# SCH_Schema_Sensoren_2022-11-04.net
KiCad netlist of a schematic drawn in EasyEDA
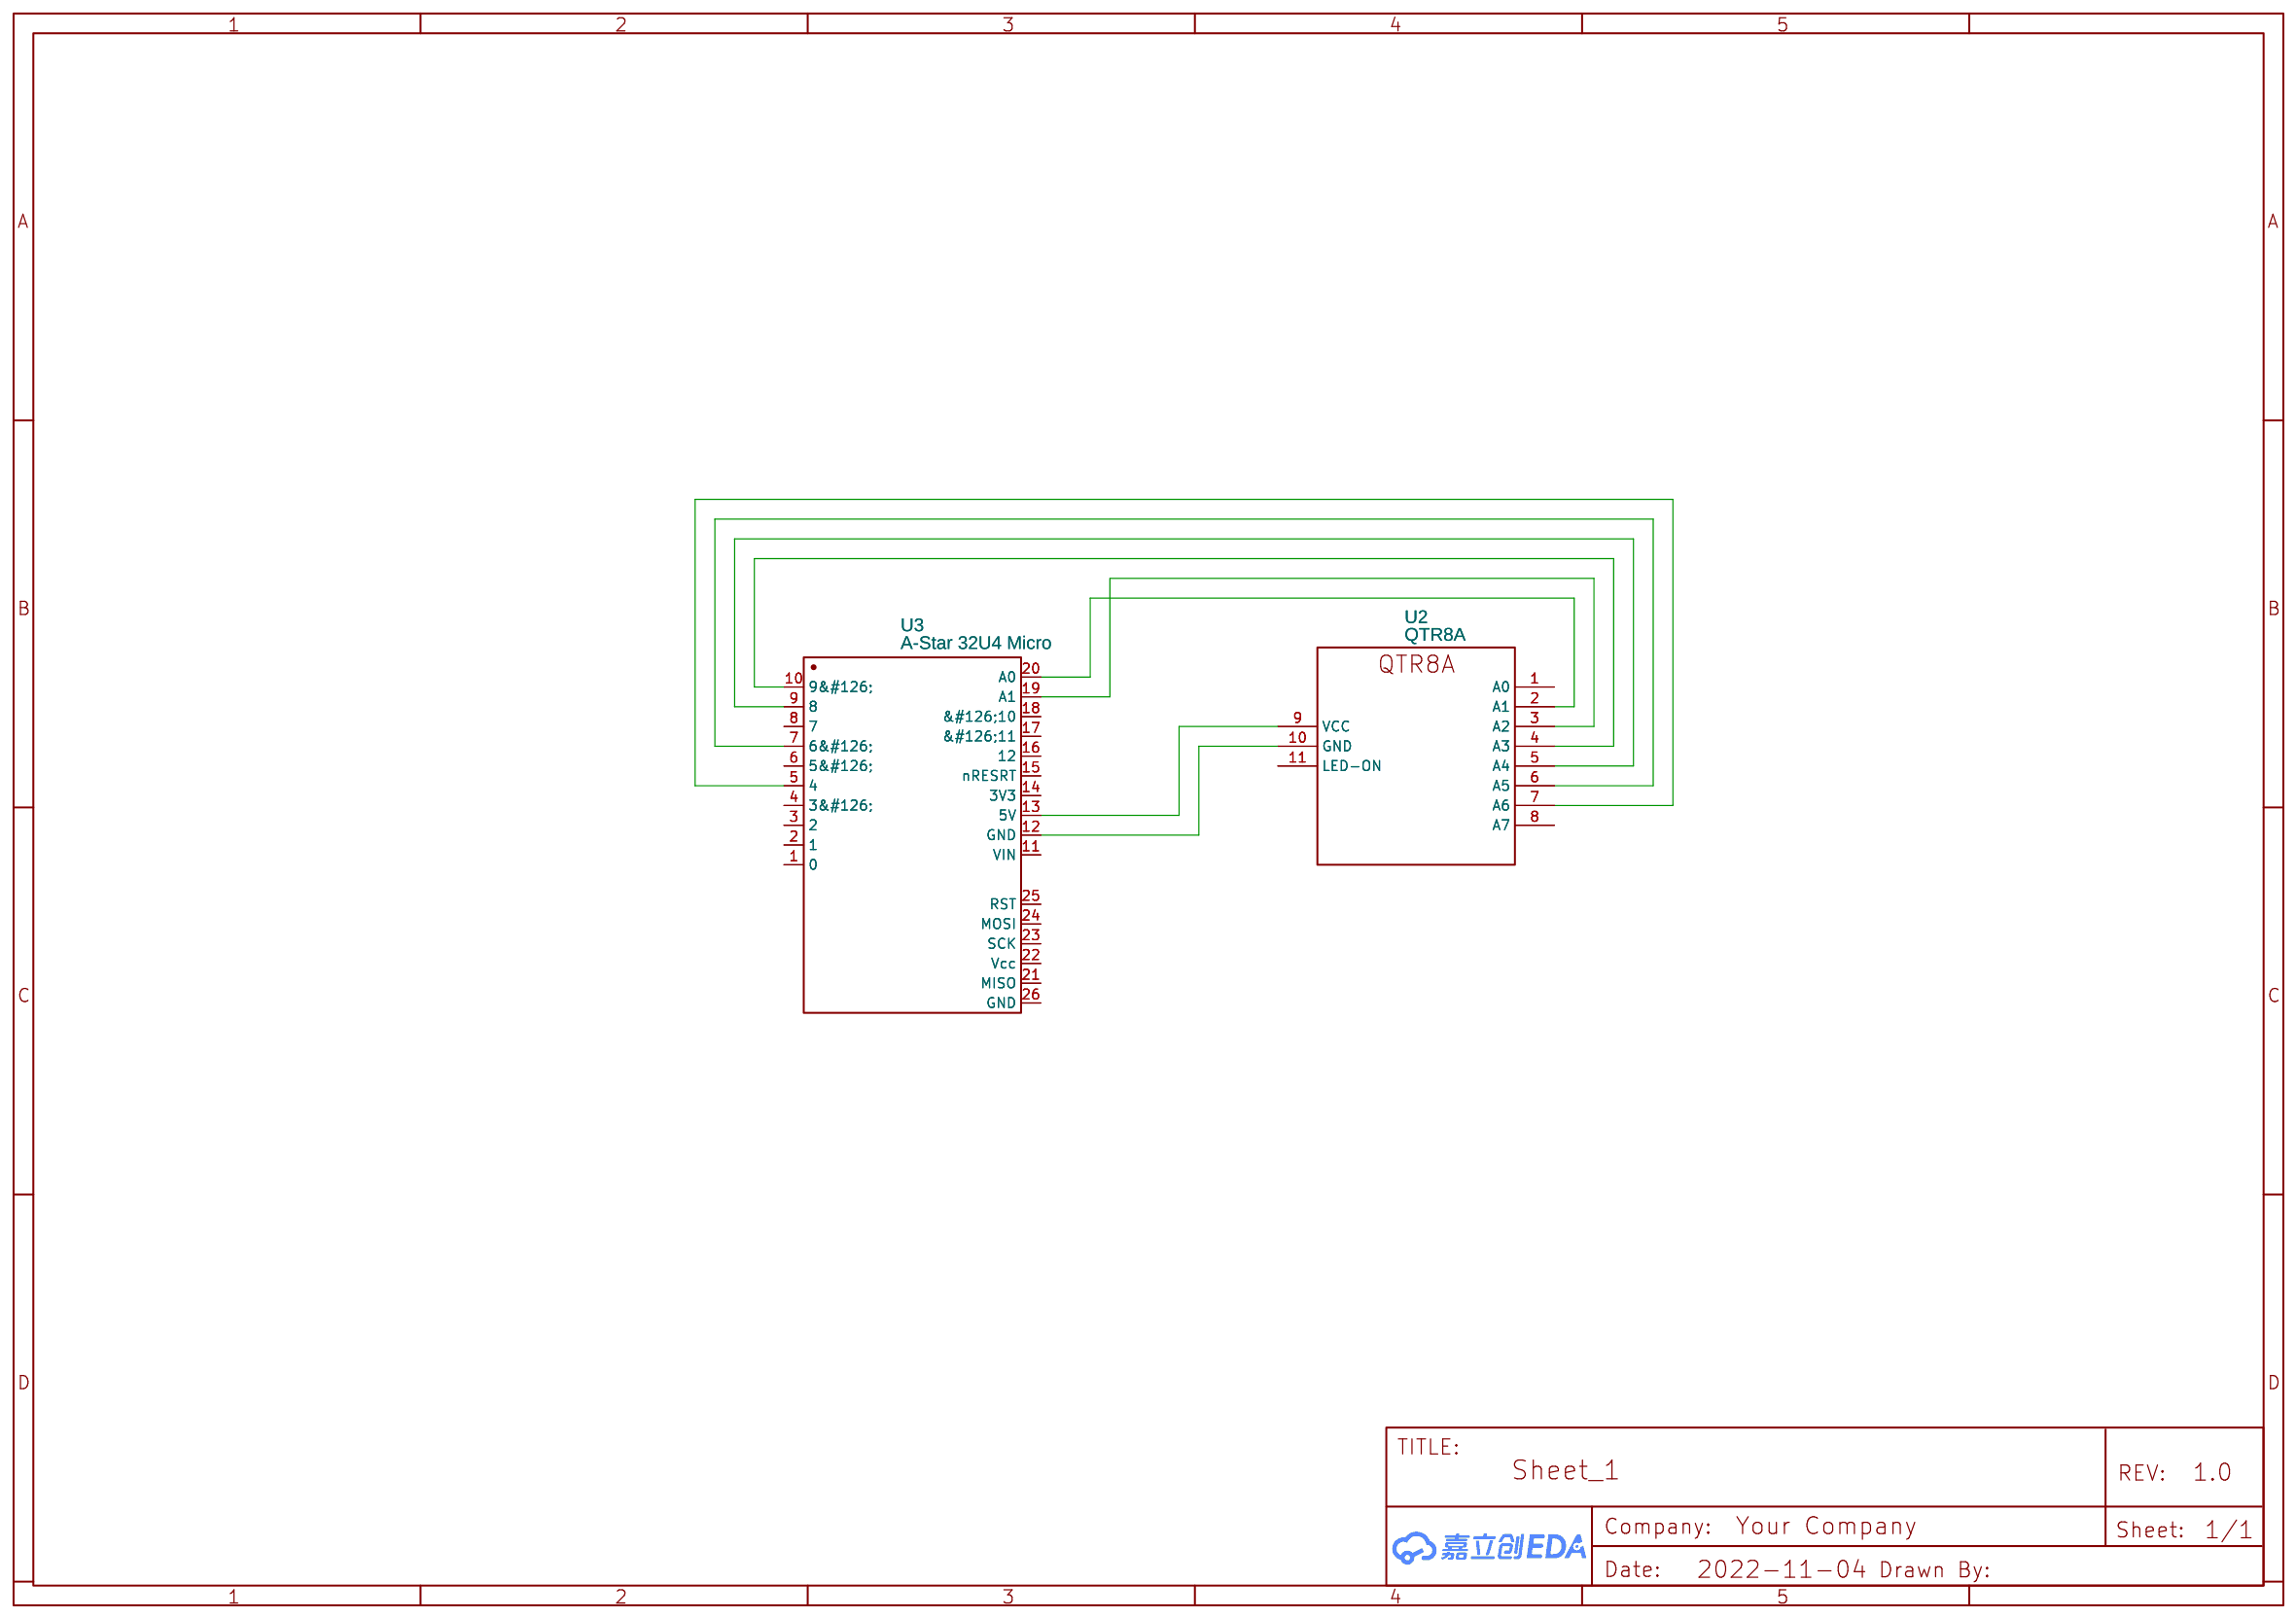
[diagram p0: schematic sheet]

(export (version "E")
  (design (tool "Eeschema 10.0.6"))
  (components
    (comp (ref "U2") (value "QTR8A") (libsource (lib "") (part "QTR8A")))
    (comp (ref "U3")
      (value "A-Star 32U4 Micro")
      (fields (field (name "BOM_Manufacturer Part") "3101"))
      (libsource (lib "") (part "A-Star 32U4 Micro"))
    )
  )
  (nets
    (net (code "1") (name "Net-(U2-A1)") (class "Default")
      (node (ref "U2") (pin "2") (pinfunction "A1_2") (pintype "unspecified"))
      (node (ref "U3") (pin "20") (pinfunction "A0_20") (pintype "unspecified"))
    )
    (net (code "2") (name "Net-(U2-A2)") (class "Default")
      (node (ref "U2") (pin "3") (pinfunction "A2_3") (pintype "unspecified"))
      (node (ref "U3") (pin "19") (pinfunction "A1_19") (pintype "unspecified"))
    )
    (net (code "3") (name "Net-(U2-A3)") (class "Default")
      (node (ref "U2") (pin "4") (pinfunction "A3_4") (pintype "unspecified"))
      (node (ref "U3") (pin "10") (pinfunction "9&#126;_10") (pintype "unspecified"))
    )
    (net (code "4") (name "Net-(U2-A4)") (class "Default")
      (node (ref "U2") (pin "5") (pinfunction "A4_5") (pintype "unspecified"))
      (node (ref "U3") (pin "9") (pinfunction "8_9") (pintype "unspecified"))
    )
    (net (code "5") (name "Net-(U2-A5)") (class "Default")
      (node (ref "U2") (pin "6") (pinfunction "A5_6") (pintype "unspecified"))
      (node (ref "U3") (pin "7") (pinfunction "6&#126;_7") (pintype "unspecified"))
    )
    (net (code "6") (name "Net-(U2-A6)") (class "Default")
      (node (ref "U2") (pin "7") (pinfunction "A6_7") (pintype "unspecified"))
      (node (ref "U3") (pin "5") (pinfunction "4_5") (pintype "unspecified"))
    )
    (net (code "7") (name "Net-(U2-GND)") (class "Default")
      (node (ref "U2") (pin "10") (pinfunction "GND_10") (pintype "unspecified"))
      (node (ref "U3") (pin "12") (pinfunction "GND_12") (pintype "unspecified"))
    )
    (net (code "8") (name "Net-(U2-VCC)") (class "Default")
      (node (ref "U2") (pin "9") (pinfunction "VCC_9") (pintype "unspecified"))
      (node (ref "U3") (pin "13") (pinfunction "5V_13") (pintype "unspecified"))
    )
    (net (code "9") (name "unconnected-(U2-A0-Pad1)") (class "Default")
      (node (ref "U2") (pin "1") (pinfunction "A0_1") (pintype "unspecified"))
    )
    (net (code "10") (name "unconnected-(U2-A7-Pad8)") (class "Default")
      (node (ref "U2") (pin "8") (pinfunction "A7_8") (pintype "unspecified"))
    )
    (net (code "11") (name "unconnected-(U2-LED-ON-Pad11)") (class "Default")
      (node (ref "U2") (pin "11") (pinfunction "LED-ON_11") (pintype "unspecified"))
    )
    (net (code "12") (name "unconnected-(U3-&#126;10-Pad18)") (class "Default")
      (node (ref "U3") (pin "18") (pinfunction "&#126;10_18") (pintype "unspecified"))
    )
    (net (code "13") (name "unconnected-(U3-&#126;11-Pad17)") (class "Default")
      (node (ref "U3") (pin "17") (pinfunction "&#126;11_17") (pintype "unspecified"))
    )
    (net (code "14") (name "unconnected-(U3-0-Pad1)") (class "Default")
      (node (ref "U3") (pin "1") (pinfunction "0_1") (pintype "unspecified"))
    )
    (net (code "15") (name "unconnected-(U3-1-Pad2)") (class "Default")
      (node (ref "U3") (pin "2") (pinfunction "1_2") (pintype "unspecified"))
    )
    (net (code "16") (name "unconnected-(U3-2-Pad3)") (class "Default")
      (node (ref "U3") (pin "3") (pinfunction "2_3") (pintype "unspecified"))
    )
    (net (code "17") (name "unconnected-(U3-3&#126;-Pad4)") (class "Default")
      (node (ref "U3") (pin "4") (pinfunction "3&#126;_4") (pintype "unspecified"))
    )
    (net (code "18") (name "unconnected-(U3-3V3-Pad14)") (class "Default")
      (node (ref "U3") (pin "14") (pinfunction "3V3_14") (pintype "unspecified"))
    )
    (net (code "19") (name "unconnected-(U3-5&#126;-Pad6)") (class "Default")
      (node (ref "U3") (pin "6") (pinfunction "5&#126;_6") (pintype "unspecified"))
    )
    (net (code "20") (name "unconnected-(U3-7-Pad8)") (class "Default")
      (node (ref "U3") (pin "8") (pinfunction "7_8") (pintype "unspecified"))
    )
    (net (code "21") (name "unconnected-(U3-12-Pad16)") (class "Default")
      (node (ref "U3") (pin "16") (pinfunction "12_16") (pintype "unspecified"))
    )
    (net (code "22") (name "unconnected-(U3-GND-Pad26)") (class "Default")
      (node (ref "U3") (pin "26") (pinfunction "GND_26") (pintype "unspecified"))
    )
    (net (code "23") (name "unconnected-(U3-MISO-Pad21)") (class "Default")
      (node (ref "U3") (pin "21") (pinfunction "MISO_21") (pintype "unspecified"))
    )
    (net (code "24") (name "unconnected-(U3-MOSI-Pad24)") (class "Default")
      (node (ref "U3") (pin "24") (pinfunction "MOSI_24") (pintype "unspecified"))
    )
    (net (code "25") (name "unconnected-(U3-RST-Pad25)") (class "Default")
      (node (ref "U3") (pin "25") (pinfunction "RST_25") (pintype "unspecified"))
    )
    (net (code "26") (name "unconnected-(U3-SCK-Pad23)") (class "Default")
      (node (ref "U3") (pin "23") (pinfunction "SCK_23") (pintype "unspecified"))
    )
    (net (code "27") (name "unconnected-(U3-VIN-Pad11)") (class "Default")
      (node (ref "U3") (pin "11") (pinfunction "VIN_11") (pintype "unspecified"))
    )
    (net (code "28") (name "unconnected-(U3-Vcc-Pad22)") (class "Default")
      (node (ref "U3") (pin "22") (pinfunction "Vcc_22") (pintype "unspecified"))
    )
    (net (code "29") (name "unconnected-(U3-nRESRT-Pad15)") (class "Default")
      (node (ref "U3") (pin "15") (pinfunction "nRESRT_15") (pintype "unspecified"))
    )
  )
)
